# MIPI-CAMERA.net
KiCad netlist of a schematic drawn in Altium Designer
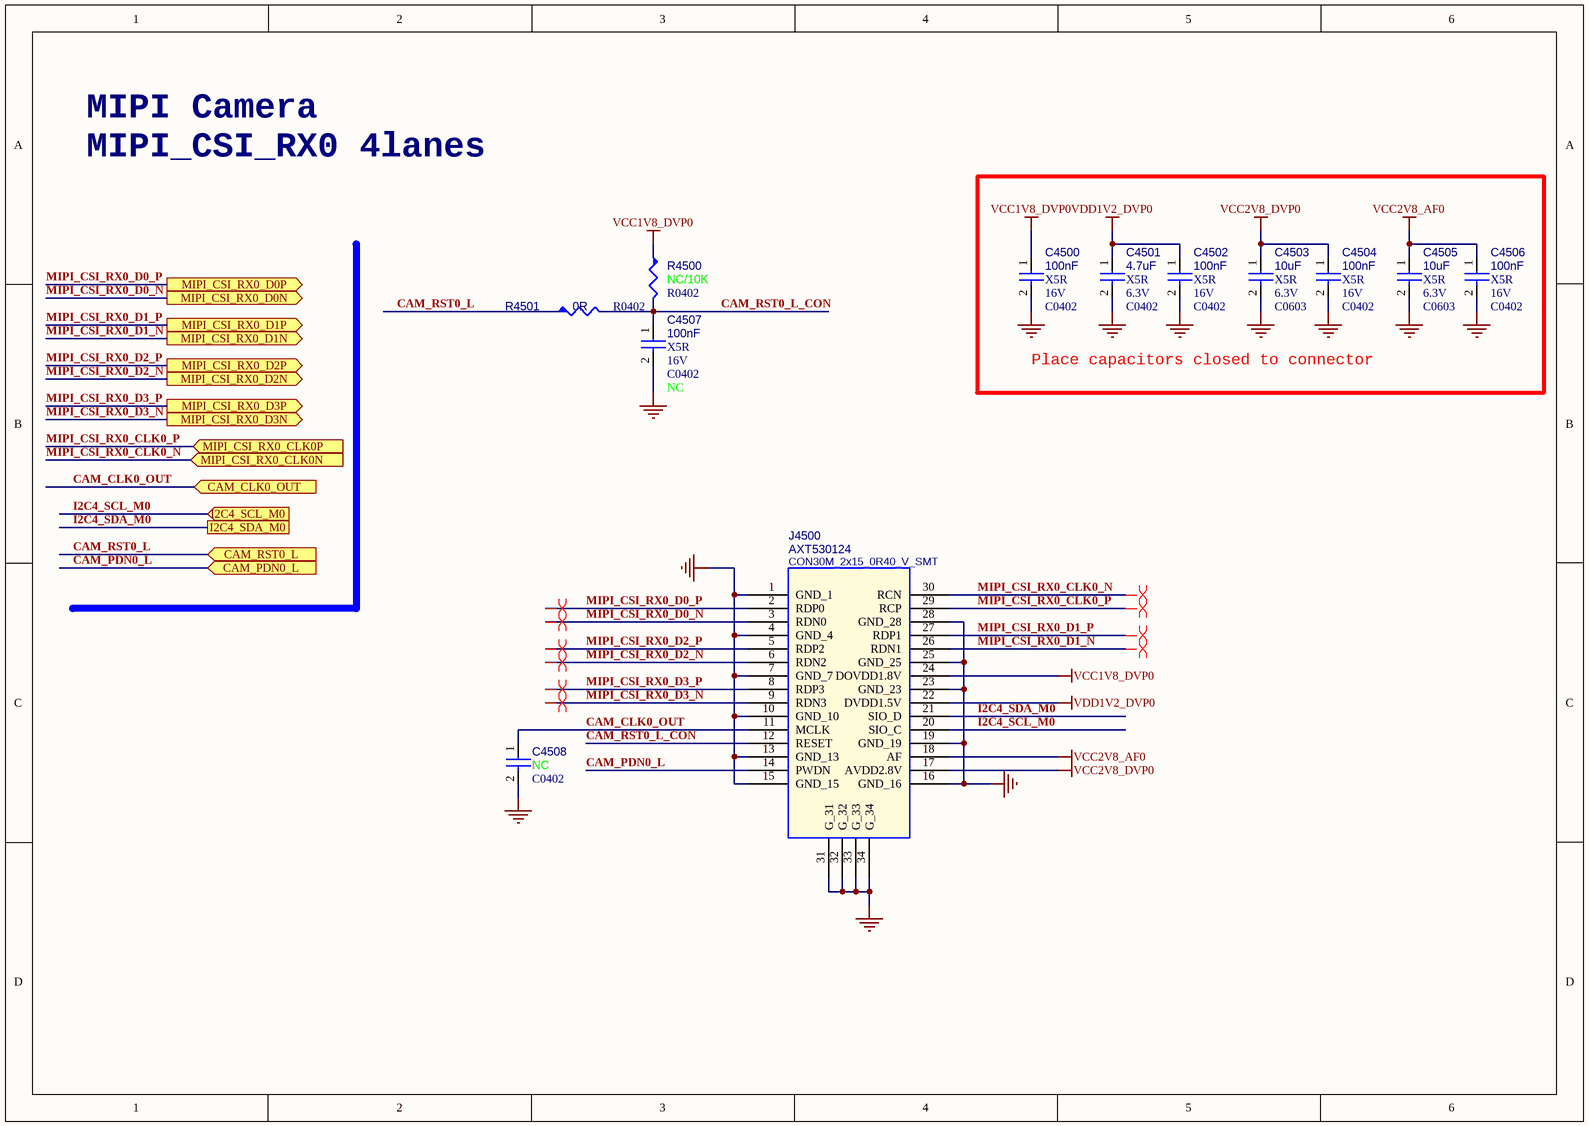
[diagram p0: MIPI-CAMERA.SchDoc]

(export (version "E")
  (design (tool "Eeschema 10.0.6"))
  (components
    (comp (ref "C4500")
      (value "100nF")
      (footprint "C0402")
      (description "cap,100.00nF,+/-10%,16V,X5R,C0402")
      (fields
        (field (name "DIELECTRIC") "X5R")
        (field (name "PCB FOOTPRINT") "C0402")
        (field (name "VOLTAGE") "16V")
        (field (name "MANUFACTURER") "TDK")
        (field (name "TOLERANCE") "10%")
        (field (name "CREATED BY") "JJJ")
      )
      (libsource (lib "*") (part "CAP NP"))
    )
    (comp (ref "C4501")
      (value "4.7uF")
      (footprint "C0402")
      (description "cap,4.70uF,+/-10%,6.3V,X5R,C0402")
      (fields
        (field (name "DIELECTRIC") "X5R")
        (field (name "PCB FOOTPRINT") "C0402")
        (field (name "VOLTAGE") "6.3V")
        (field (name "MANUFACTURER") "TDK")
        (field (name "TOLERANCE") "10%")
        (field (name "CREATED BY") "JJJ")
      )
      (libsource (lib "*") (part "CAP NP"))
    )
    (comp (ref "C4502")
      (value "100nF")
      (footprint "C0402")
      (description "cap,100.00nF,+/-10%,16V,X5R,C0402")
      (fields
        (field (name "DIELECTRIC") "X5R")
        (field (name "PCB FOOTPRINT") "C0402")
        (field (name "VOLTAGE") "16V")
        (field (name "MANUFACTURER") "TDK")
        (field (name "TOLERANCE") "10%")
        (field (name "CREATED BY") "JJJ")
      )
      (libsource (lib "*") (part "CAP NP"))
    )
    (comp (ref "C4503")
      (value "10uF")
      (footprint "C0603")
      (description "cap,10.00uF,+/-10%,6.3V,X5R,C0603")
      (fields
        (field (name "DIELECTRIC") "X5R")
        (field (name "PCB FOOTPRINT") "C0603")
        (field (name "VOLTAGE") "6.3V")
        (field (name "MANUFACTURER") "TDK")
        (field (name "TOLERANCE") "10%")
        (field (name "CREATED BY") "JJJ")
      )
      (libsource (lib "*") (part "CAP NP"))
    )
    (comp (ref "C4504")
      (value "100nF")
      (footprint "C0402")
      (description "cap,100.00nF,+/-10%,16V,X5R,C0402")
      (fields
        (field (name "DIELECTRIC") "X5R")
        (field (name "PCB FOOTPRINT") "C0402")
        (field (name "VOLTAGE") "16V")
        (field (name "TOLERANCE") "10%")
        (field (name "MANUFACTURER") "TDK")
        (field (name "CREATED BY") "JJJ")
      )
      (libsource (lib "*") (part "CAP NP"))
    )
    (comp (ref "C4505")
      (value "10uF")
      (footprint "C0603")
      (description "cap,10.00uF,+/-10%,6.3V,X5R,C0603")
      (fields
        (field (name "DIELECTRIC") "X5R")
        (field (name "PCB FOOTPRINT") "C0603")
        (field (name "VOLTAGE") "6.3V")
        (field (name "TOLERANCE") "10%")
        (field (name "MANUFACTURER") "TDK")
        (field (name "CREATED BY") "JJJ")
      )
      (libsource (lib "*") (part "CAP NP"))
    )
    (comp (ref "C4506")
      (value "100nF")
      (footprint "C0402")
      (description "cap,100.00nF,+/-10%,16V,X5R,C0402")
      (fields
        (field (name "DIELECTRIC") "X5R")
        (field (name "PCB FOOTPRINT") "C0402")
        (field (name "VOLTAGE") "16V")
        (field (name "TOLERANCE") "10%")
        (field (name "MANUFACTURER") "TDK")
        (field (name "CREATED BY") "JJJ")
      )
      (libsource (lib "*") (part "CAP NP"))
    )
    (comp (ref "C4507")
      (value "100nF")
      (footprint "C0402")
      (description "cap,100.00nF,+/-10%,16V,X5R,C0402")
      (fields
        (field (name "DIELECTRIC") "X5R")
        (field (name "PCB FOOTPRINT") "C0402")
        (field (name "VOLTAGE") "16V")
        (field (name "MANUFACTURER") "TDK")
        (field (name "TOLERANCE") "10%")
        (field (name "OPTION") "NC")
        (field (name "CREATED BY") "JJJ")
      )
      (libsource (lib "*") (part "CAP NP"))
    )
    (comp (ref "C4508")
      (value "NC")
      (footprint "C0402")
      (description "NC电容，无容值.")
      (fields (field (name "PCB FOOTPRINT") "C0402") (field (name "CREATED BY") "JJJ"))
      (libsource (lib "*") (part "CAP NP_NC"))
    )
    (comp (ref "J4500")
      (value "AXT530124")
      (footprint "CONN-SMD_30P-P0.40_AXT530124")
      (description "Rockchips内部通用双排30PIN for MIPI CSI摄像头接口；")
      (fields
        (field (name "PCB FOOTPRINT") "CON30M_2x15_0R40_V_SMT")
        (field (name "MANUFACTURER") "Panasonic")
        (field (name "CREATED BY") "JJJ")
      )
      (libsource (lib "RK3562_REF") (part "CMK-CB0077-FV1_2"))
    )
    (comp (ref "R4500")
      (value "NC/10K")
      (footprint "R0402")
      (description "通用厚膜电阻,10K,+/-5%,R0402,1/16W.")
      (fields
        (field (name "PCB FOOTPRINT") "R0402")
        (field (name "TOLERANCE") "5%")
        (field (name "MANUFACTURER") "YAGEO")
        (field (name "CREATED BY") "YTL")
      )
      (libsource (lib "*") (part "RESISTOR5_NC"))
    )
    (comp (ref "R4501")
      (value "0R")
      (footprint "R0402")
      (description "通用厚膜电阻,0R,+/-5%,R0402,1/16W.")
      (fields
        (field (name "TOLERANCE") "5%")
        (field (name "PCB FOOTPRINT") "R0402")
        (field (name "MANUFACTURER") "YAGEO")
        (field (name "CREATED BY") "YTL")
      )
      (libsource (lib "*") (part "RESISTOR5"))
    )
  )
  (nets
    (net (code "1") (name "/CAM_CLK0_OUT") (class "Default")
      (node (ref "C4508") (pin "1") (pinfunction "1_1") (pintype "passive"))
      (node (ref "J4500") (pin "11") (pinfunction "MCLK_11") (pintype "passive"))
    )
    (net (code "2") (name "/CAM_PDN0_L") (class "Default")
      (node (ref "J4500") (pin "14") (pinfunction "PWDN_14") (pintype "passive"))
    )
    (net (code "3") (name "/CAM_RST0_L") (class "Default")
      (node (ref "R4501") (pin "1") (pinfunction "1_1") (pintype "passive"))
    )
    (net (code "4") (name "/CAM_RST0_L_CON") (class "Default")
      (node (ref "C4507") (pin "1") (pinfunction "1_1") (pintype "passive"))
      (node (ref "J4500") (pin "12") (pinfunction "RESET_12") (pintype "passive"))
      (node (ref "R4500") (pin "2") (pinfunction "2_2") (pintype "passive"))
      (node (ref "R4501") (pin "2") (pinfunction "2_2") (pintype "passive"))
    )
    (net (code "5") (name "/I2C4_SCL_M0") (class "Default")
      (node (ref "J4500") (pin "20") (pinfunction "SIO_C_20") (pintype "passive"))
    )
    (net (code "6") (name "/I2C4_SDA_M0") (class "Default")
      (node (ref "J4500") (pin "21") (pinfunction "SIO_D_21") (pintype "passive"))
    )
    (net (code "7") (name "/MIPI_CSI_RX0_CLK0_N") (class "Default")
      (node (ref "J4500") (pin "30") (pinfunction "RCN_30") (pintype "passive"))
    )
    (net (code "8") (name "/MIPI_CSI_RX0_CLK0_P") (class "Default")
      (node (ref "J4500") (pin "29") (pinfunction "RCP_29") (pintype "passive"))
    )
    (net (code "9") (name "/MIPI_CSI_RX0_D0_N") (class "Default")
      (node (ref "J4500") (pin "3") (pinfunction "RDN0_3") (pintype "passive"))
    )
    (net (code "10") (name "/MIPI_CSI_RX0_D0_P") (class "Default")
      (node (ref "J4500") (pin "2") (pinfunction "RDP0_2") (pintype "passive"))
    )
    (net (code "11") (name "/MIPI_CSI_RX0_D1_N") (class "Default")
      (node (ref "J4500") (pin "26") (pinfunction "RDN1_26") (pintype "passive"))
    )
    (net (code "12") (name "/MIPI_CSI_RX0_D1_P") (class "Default")
      (node (ref "J4500") (pin "27") (pinfunction "RDP1_27") (pintype "passive"))
    )
    (net (code "13") (name "/MIPI_CSI_RX0_D2_N") (class "Default")
      (node (ref "J4500") (pin "6") (pinfunction "RDN2_6") (pintype "passive"))
    )
    (net (code "14") (name "/MIPI_CSI_RX0_D2_P") (class "Default")
      (node (ref "J4500") (pin "5") (pinfunction "RDP2_5") (pintype "passive"))
    )
    (net (code "15") (name "/MIPI_CSI_RX0_D3_N") (class "Default")
      (node (ref "J4500") (pin "9") (pinfunction "RDN3_9") (pintype "passive"))
    )
    (net (code "16") (name "/MIPI_CSI_RX0_D3_P") (class "Default")
      (node (ref "J4500") (pin "8") (pinfunction "RDP3_8") (pintype "passive"))
    )
    (net (code "17") (name "GND") (class "Default")
      (node (ref "C4500") (pin "2") (pinfunction "2_2") (pintype "passive"))
      (node (ref "C4501") (pin "2") (pinfunction "2_2") (pintype "passive"))
      (node (ref "C4502") (pin "2") (pinfunction "2_2") (pintype "passive"))
      (node (ref "C4503") (pin "2") (pinfunction "2_2") (pintype "passive"))
      (node (ref "C4504") (pin "2") (pinfunction "2_2") (pintype "passive"))
      (node (ref "C4505") (pin "2") (pinfunction "2_2") (pintype "passive"))
      (node (ref "C4506") (pin "2") (pinfunction "2_2") (pintype "passive"))
      (node (ref "C4507") (pin "2") (pinfunction "2_2") (pintype "passive"))
      (node (ref "C4508") (pin "2") (pinfunction "2_2") (pintype "passive"))
      (node (ref "J4500") (pin "1") (pinfunction "GND_1_1") (pintype "passive"))
      (node (ref "J4500") (pin "10") (pinfunction "GND_10_10") (pintype "passive"))
      (node (ref "J4500") (pin "13") (pinfunction "GND_13_13") (pintype "passive"))
      (node (ref "J4500") (pin "15") (pinfunction "GND_15_15") (pintype "passive"))
      (node (ref "J4500") (pin "16") (pinfunction "GND_16_16") (pintype "passive"))
      (node (ref "J4500") (pin "19") (pinfunction "GND_19_19") (pintype "passive"))
      (node (ref "J4500") (pin "23") (pinfunction "GND_23_23") (pintype "passive"))
      (node (ref "J4500") (pin "25") (pinfunction "GND_25_25") (pintype "passive"))
      (node (ref "J4500") (pin "28") (pinfunction "GND_28_28") (pintype "passive"))
      (node (ref "J4500") (pin "31") (pinfunction "G_31_31") (pintype "passive"))
      (node (ref "J4500") (pin "32") (pinfunction "G_32_32") (pintype "passive"))
      (node (ref "J4500") (pin "33") (pinfunction "G_33_33") (pintype "passive"))
      (node (ref "J4500") (pin "34") (pinfunction "G_34_34") (pintype "passive"))
      (node (ref "J4500") (pin "4") (pinfunction "GND_4_4") (pintype "passive"))
      (node (ref "J4500") (pin "7") (pinfunction "GND_7_7") (pintype "passive"))
    )
    (net (code "18") (name "VCC1V8_DVP0") (class "Default")
      (node (ref "C4500") (pin "1") (pinfunction "1_1") (pintype "passive"))
      (node (ref "J4500") (pin "24") (pinfunction "DOVDD1.8V_24") (pintype "passive"))
      (node (ref "R4500") (pin "1") (pinfunction "1_1") (pintype "passive"))
    )
    (net (code "19") (name "VCC2V8_AF0") (class "Default")
      (node (ref "C4505") (pin "1") (pinfunction "1_1") (pintype "passive"))
      (node (ref "C4506") (pin "1") (pinfunction "1_1") (pintype "passive"))
      (node (ref "J4500") (pin "18") (pinfunction "AF_18") (pintype "passive"))
    )
    (net (code "20") (name "VCC2V8_DVP0") (class "Default")
      (node (ref "C4503") (pin "1") (pinfunction "1_1") (pintype "passive"))
      (node (ref "C4504") (pin "1") (pinfunction "1_1") (pintype "passive"))
      (node (ref "J4500") (pin "17") (pinfunction "AVDD2.8V_17") (pintype "passive"))
    )
    (net (code "21") (name "VDD1V2_DVP0") (class "Default")
      (node (ref "C4501") (pin "1") (pinfunction "1_1") (pintype "passive"))
      (node (ref "C4502") (pin "1") (pinfunction "1_1") (pintype "passive"))
      (node (ref "J4500") (pin "22") (pinfunction "DVDD1.5V_22") (pintype "passive"))
    )
  )
)
